# STM32F103T8.net
KiCad netlist of a schematic drawn in Altium Designer
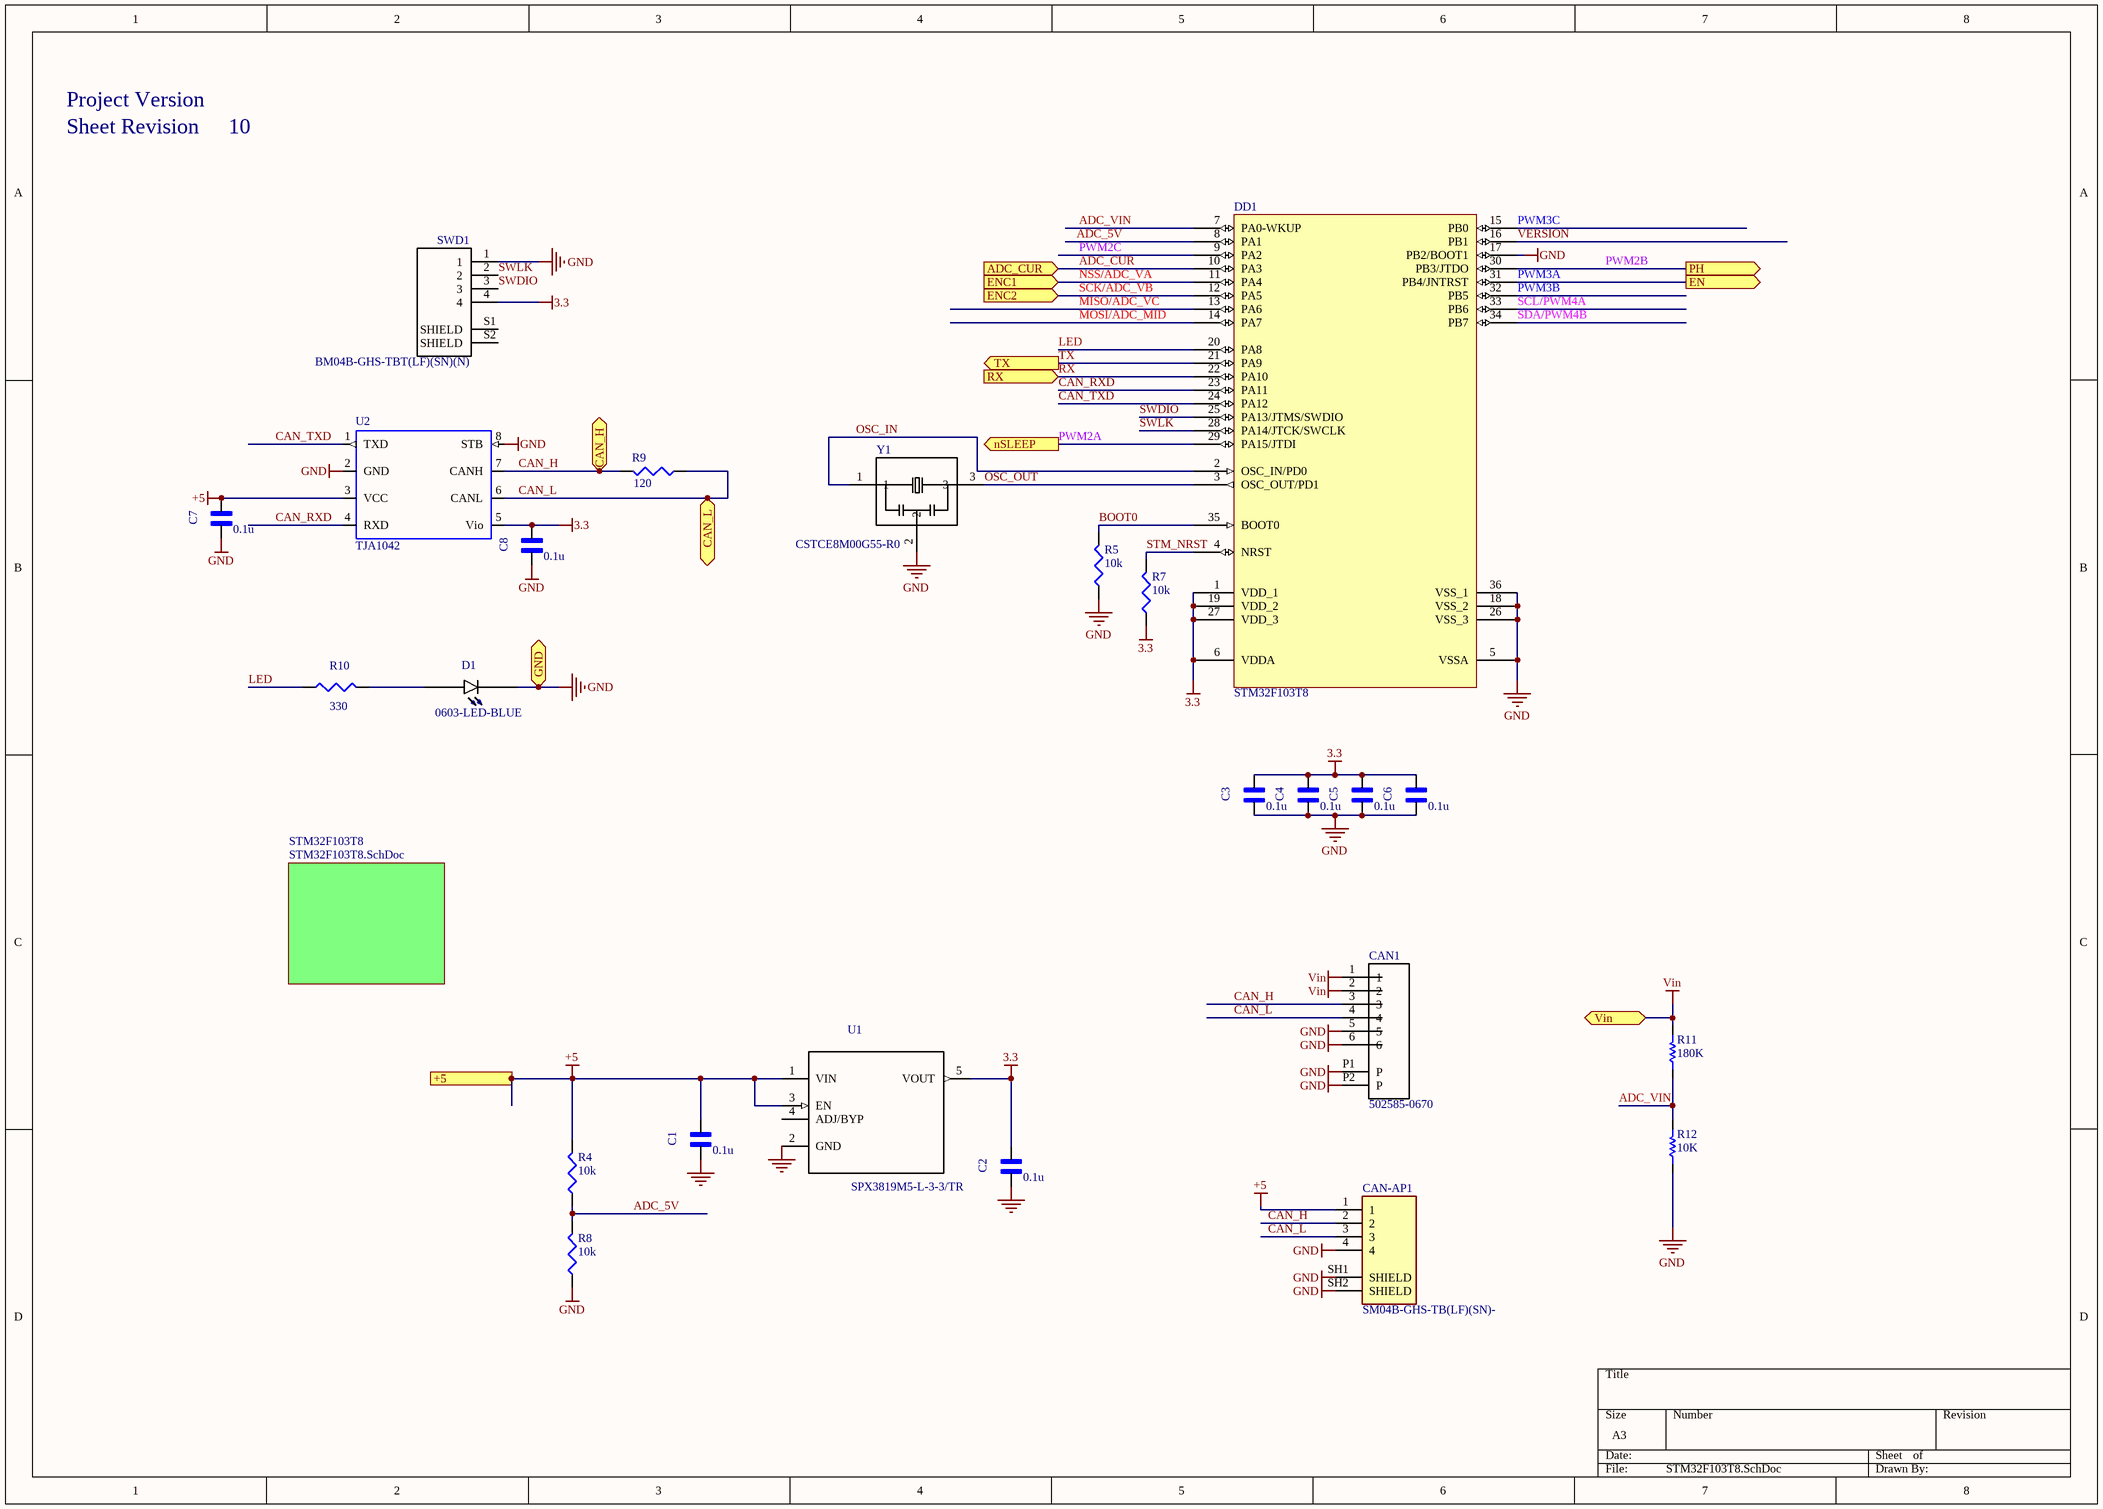
[diagram p0: STM32F103T8.SchDoc]

(export (version "E")
  (design (tool "Eeschema 10.0.6"))
  (components
    (comp (ref "C1")
      (value "0.1u")
      (footprint "*CAPC1608X90")
      (description "Cap Thin Film 0.1uf 50v 0603")
      (fields (field (name "MF") "AVX") (field (name "MP") "GX035C104MAT2-500"))
      (libsource (lib "lib") (part "GX035C104MAT2-500"))
    )
    (comp (ref "C2")
      (value "0.1u")
      (footprint "*CAPC1608X90")
      (description "Cap Thin Film 0.1uf 50v 0603")
      (fields (field (name "MF") "AVX") (field (name "MP") "GX035C104MAT2-500"))
      (libsource (lib "lib") (part "GX035C104MAT2-500"))
    )
    (comp (ref "C3")
      (value "0.1u")
      (footprint "*CAPC1608X90")
      (description "Cap Thin Film 0.1uf 50v 0603")
      (fields (field (name "MF") "AVX") (field (name "MP") "GX035C104MAT2-500 or CL10B104JB8NNNC"))
      (libsource (lib "lib") (part "GX035C104MAT2-500"))
    )
    (comp (ref "C4")
      (value "0.1u")
      (footprint "*CAPC1608X90")
      (description "Cap Thin Film 0.1uf 50v 0603")
      (fields (field (name "MF") "AVX") (field (name "MP") "GX035C104MAT2-500 or CL10B104JB8NNNC"))
      (libsource (lib "lib") (part "GX035C104MAT2-500"))
    )
    (comp (ref "C5")
      (value "0.1u")
      (footprint "*CAPC1608X90")
      (description "Cap Thin Film 0.1uf 50v 0603")
      (fields (field (name "MF") "AVX") (field (name "MP") "GX035C104MAT2-500 or CL10B104JB8NNNC"))
      (libsource (lib "lib") (part "GX035C104MAT2-500"))
    )
    (comp (ref "C6")
      (value "0.1u")
      (footprint "*CAPC1608X90")
      (description "Cap Thin Film 0.1uf 50v 0603")
      (fields (field (name "MF") "AVX") (field (name "MP") "GX035C104MAT2-500 or CL10B104JB8NNNC"))
      (libsource (lib "lib") (part "GX035C104MAT2-500"))
    )
    (comp (ref "C7")
      (value "0.1u")
      (footprint "*CAPC1608X90")
      (description "Cap Thin Film 0.1uf 50v 0603")
      (fields (field (name "MF") "AVX") (field (name "MP") "GX035C104MAT2-500 or CL10B104JB8NNNC"))
      (libsource (lib "lib") (part "GX035C104MAT2-500"))
    )
    (comp (ref "C8")
      (value "0.1u")
      (footprint "*CAPC1608X90")
      (description "Cap Thin Film 0.1uf 50v 0603")
      (fields (field (name "MF") "AVX") (field (name "MP") "GX035C104MAT2-500 or CL10B104JB8NNNC"))
      (libsource (lib "lib") (part "GX035C104MAT2-500"))
    )
    (comp (ref "CAN-AP1")
      (value "SM04B-GHS-TB(LF)(SN)-")
      (footprint "JST_SM04B-GHS-TB(LF)(SN)-")
      (description "Connector Header Surface Mount, Right Angle 4 position 0.049 _1.25mm_")
      (fields (field (name "MP") "SM04B-GHS-TB(LF)(SN)") (field (name "MF") "JST Sales"))
      (libsource (lib "lib") (part "SM04B-GHS-TB(LF)(SN)-"))
    )
    (comp (ref "CAN1")
      (value "502585-0670")
      (footprint "MOLEX_502585-0670")
      (fields (field (name "MF") "Molex"))
      (libsource (lib "lib") (part "502585-0670"))
    )
    (comp (ref "D1")
      (value "0603-LED-BLUE")
      (footprint "*LEDM1608X80_LTE-C1906R-14(Primary)")
      (description "LED IrLED Chip LED 2-Pin SMD T/R")
      (libsource (lib "lib") (part "LTE-C1906R-14"))
    )
    (comp (ref "DD1")
      (value "STM32F103T8")
      (footprint "*QFN50P600X600X100-37N")
      (description "STM32F103T8U6, Микроконтроллер 32BIT ARM 64K FLASH [VFQFPN-36]")
      (fields (field (name "MF") "STM") (field (name "MP") "STM32F103T8U6"))
      (libsource (lib "lib") (part "STM32F103T8"))
    )
    (comp (ref "R4")
      (value "10k")
      (footprint "J1-0603")
      (description "10 kOhms 1 0.1 W 1 10 W Chip Resistor 0603 1608 Metric Thick Film")
      (fields (field (name "MF") "Yageo or NXP") (field (name "MP") "10K 1% 0603"))
      (libsource (lib "CAN_NODE_MINI") (part "RC0603FR-0710KL"))
    )
    (comp (ref "R5")
      (value "10k")
      (footprint "J1-0603")
      (description "10 kOhms 1 0.1 W 1 10 W Chip Resistor 0603 1608 Metric Thick Film")
      (fields (field (name "MF") "Yageo or NXP") (field (name "MP") "10K 1% 0603"))
      (libsource (lib "CAN_NODE_MINI") (part "RC0603FR-0710KL"))
    )
    (comp (ref "R7")
      (value "10k")
      (footprint "J1-0603")
      (description "10 kOhms 1 0.1 W 1 10 W Chip Resistor 0603 1608 Metric Thick Film")
      (fields (field (name "MF") "Yageo or NXP") (field (name "MP") "10K 1% 0603"))
      (libsource (lib "CAN_NODE_MINI") (part "RC0603FR-0710KL"))
    )
    (comp (ref "R8")
      (value "10k")
      (footprint "J1-0603")
      (description "10 kOhms 1 0.1 W 1 10 W Chip Resistor 0603 1608 Metric Thick Film")
      (fields (field (name "MF") "Yageo or NXP") (field (name "MP") "10K 1% 0603"))
      (libsource (lib "CAN_NODE_MINI") (part "RC0603FR-0710KL"))
    )
    (comp (ref "R9")
      (value "120")
      (footprint "J1-0603")
      (description "120 Ohms 1 0.1 W 1 10 W Chip Resistor 0603 1608 Metric Thick Film")
      (fields (field (name "MP") "RC0603FR-07120RL") (field (name "Comment") "Res3"))
      (libsource (lib "Miscellaneous Devices") (part "Res3"))
    )
    (comp (ref "R10")
      (value "330")
      (footprint "J1-0603")
      (description "Resistor")
      (fields (field (name "MP") "RC0603FR-07330RL") (field (name "Comment") "Res3"))
      (libsource (lib "Miscellaneous Devices") (part "Res3"))
    )
    (comp (ref "R11")
      (value "180K")
      (footprint "RES 0603 (1608X06L)")
      (description "Resistor")
      (fields (field (name "TOLERANCE") "5%") (field (name "POWER") "1/8 W"))
      (libsource (lib "R2T Team Library") (part "Resistor"))
    )
    (comp (ref "R12")
      (value "10K")
      (footprint "RES 0603 (1608X06L)")
      (description "Resistor")
      (fields (field (name "TOLERANCE") "5%") (field (name "POWER") "1/8 W"))
      (libsource (lib "R2T Team Library") (part "Resistor"))
    )
    (comp (ref "SWD1")
      (value "BM04B-GHS-TBT(LF)(SN)(N)")
      (footprint "JST_BM04B-GHS-holes")
      (description "Conn Shrouded Header HDR 4 POS 1.25mm Solder ST SMD Reel")
      (fields (field (name "MF") "JST Sales") (field (name "MP") "SM04B-GHS-TB(LF)(SN)"))
      (libsource (lib "lib") (part "BM04B-GHS-TBT(LF)(SN)(N)"))
    )
    (comp (ref "U1")
      (value "SPX3819M5-L-3-3/TR")
      (footprint "*SOT95P280X145-5N")
      (description "Low Dropout Voltage Regulator, Adjustable 0.5A, В±1%, 2.5 to 16 Vin, 5-Pin SOT-23")
      (fields (field (name "MF") "MaxLinear, Inc."))
      (libsource (lib "DC_DC") (part "SPX3819M5-L"))
    )
    (comp (ref "U2")
      (value "TJA1042")
      (footprint "SOT782-1")
      (description "1/1 Transceiver Half CANbus 8-SO")
      (fields (field (name "MF") "NXP USA"))
      (libsource (lib "lib") (part "TJA1042"))
    )
    (comp (ref "Y1")
      (value "CSTCE8M00G55-R0")
      (footprint "*OSC_CSTCE8M00G55-R0")
      (description "Ceramic Resonator 8MHz ??0.5% _Tol_ ??0.2% _Stability_ 33pF 40Ohm 3-Pin CSMD T/R")
      (fields (field (name "MF") "Murata"))
      (libsource (lib "DC_DC") (part "CSTCE8M00G55-R0"))
    )
  )
  (nets
    (net (code "1") (name "+5") (class "Default")
      (node (ref "C1") (pin "1") (pinfunction "1_1") (pintype "passive"))
      (node (ref "C7") (pin "1") (pinfunction "1_1") (pintype "passive"))
      (node (ref "CAN-AP1") (pin "1") (pinfunction "1_1") (pintype "passive"))
      (node (ref "R4") (pin "2") (pinfunction "2_2") (pintype "passive"))
      (node (ref "U1") (pin "1") (pinfunction "VIN_1") (pintype "power_in"))
      (node (ref "U1") (pin "3") (pinfunction "EN_3") (pintype "input"))
      (node (ref "U2") (pin "3") (pinfunction "VCC_3") (pintype "power_in"))
    )
    (net (code "2") (name "/ADC_5V") (class "Default")
      (node (ref "DD1") (pin "8") (pinfunction "PA1_8") (pintype "bidirectional"))
      (node (ref "R4") (pin "1") (pinfunction "1_1") (pintype "passive"))
      (node (ref "R8") (pin "2") (pinfunction "2_2") (pintype "passive"))
    )
    (net (code "3") (name "/ADC_CUR") (class "Default")
      (node (ref "DD1") (pin "10") (pinfunction "PA3_10") (pintype "bidirectional"))
    )
    (net (code "4") (name "/ADC_VIN") (class "Default")
      (node (ref "DD1") (pin "7") (pinfunction "PA0-WKUP_7") (pintype "bidirectional"))
      (node (ref "R11") (pin "1") (pinfunction "1_1") (pintype "passive"))
      (node (ref "R12") (pin "2") (pinfunction "2_2") (pintype "passive"))
    )
    (net (code "5") (name "/BOOT0") (class "Default")
      (node (ref "DD1") (pin "35") (pinfunction "BOOT0_35") (pintype "input"))
      (node (ref "R5") (pin "2") (pinfunction "2_2") (pintype "passive"))
    )
    (net (code "6") (name "/CAN_H") (class "Default")
      (node (ref "CAN-AP1") (pin "2") (pinfunction "2_2") (pintype "passive"))
      (node (ref "CAN1") (pin "3") (pinfunction "3_3") (pintype "passive"))
      (node (ref "R9") (pin "2") (pinfunction "2_2") (pintype "passive"))
      (node (ref "U2") (pin "7") (pinfunction "CANH_7") (pintype "bidirectional"))
    )
    (net (code "7") (name "/CAN_L") (class "Default")
      (node (ref "CAN-AP1") (pin "3") (pinfunction "3_3") (pintype "passive"))
      (node (ref "CAN1") (pin "4") (pinfunction "4_4") (pintype "passive"))
      (node (ref "R9") (pin "1") (pinfunction "1_1") (pintype "passive"))
      (node (ref "U2") (pin "6") (pinfunction "CANL_6") (pintype "bidirectional"))
    )
    (net (code "8") (name "/CAN_RXD") (class "Default")
      (node (ref "DD1") (pin "23") (pinfunction "PA11_23") (pintype "bidirectional"))
      (node (ref "U2") (pin "4") (pinfunction "RXD_4") (pintype "bidirectional"))
    )
    (net (code "9") (name "/CAN_TXD") (class "Default")
      (node (ref "DD1") (pin "24") (pinfunction "PA12_24") (pintype "bidirectional"))
      (node (ref "U2") (pin "1") (pinfunction "TXD_1") (pintype "output"))
    )
    (net (code "10") (name "/EN") (class "Default")
      (node (ref "DD1") (pin "31") (pinfunction "PB4/JNTRST_31") (pintype "bidirectional"))
    )
    (net (code "11") (name "/LED") (class "Default")
      (node (ref "DD1") (pin "20") (pinfunction "PA8_20") (pintype "bidirectional"))
      (node (ref "R10") (pin "1") (pinfunction "1_1") (pintype "passive"))
    )
    (net (code "12") (name "/MISO{slash}ADC_VC") (class "Default")
      (node (ref "DD1") (pin "13") (pinfunction "PA6_13") (pintype "bidirectional"))
    )
    (net (code "13") (name "/MOSI{slash}ADC_MID") (class "Default")
      (node (ref "DD1") (pin "14") (pinfunction "PA7_14") (pintype "bidirectional"))
    )
    (net (code "14") (name "/NSS{slash}ADC_VA") (class "Default")
      (node (ref "DD1") (pin "11") (pinfunction "PA4_11") (pintype "bidirectional"))
    )
    (net (code "15") (name "/OSC_IN") (class "Default")
      (node (ref "DD1") (pin "2") (pinfunction "OSC_IN/PD0_2") (pintype "input"))
      (node (ref "Y1") (pin "1") (pinfunction "1_1") (pintype "passive"))
    )
    (net (code "16") (name "/OSC_OUT") (class "Default")
      (node (ref "DD1") (pin "3") (pinfunction "OSC_OUT/PD1_3") (pintype "output"))
      (node (ref "Y1") (pin "3") (pinfunction "3_3") (pintype "passive"))
    )
    (net (code "17") (name "/PH") (class "Default")
      (node (ref "DD1") (pin "30") (pinfunction "PB3/JTDO_30") (pintype "bidirectional"))
    )
    (net (code "18") (name "/PWM2A") (class "Default")
      (node (ref "DD1") (pin "29") (pinfunction "PA15/JTDI_29") (pintype "bidirectional"))
    )
    (net (code "20") (name "/PWM2C") (class "Default")
      (node (ref "DD1") (pin "9") (pinfunction "PA2_9") (pintype "bidirectional"))
    )
    (net (code "22") (name "/PWM3B") (class "Default")
      (node (ref "DD1") (pin "32") (pinfunction "PB5_32") (pintype "bidirectional"))
    )
    (net (code "23") (name "/PWM3C") (class "Default")
      (node (ref "DD1") (pin "15") (pinfunction "PB0_15") (pintype "bidirectional"))
    )
    (net (code "24") (name "/RX") (class "Default")
      (node (ref "DD1") (pin "22") (pinfunction "PA10_22") (pintype "bidirectional"))
    )
    (net (code "25") (name "/SCK{slash}ADC_VB") (class "Default")
      (node (ref "DD1") (pin "12") (pinfunction "PA5_12") (pintype "bidirectional"))
    )
    (net (code "26") (name "/SCL{slash}PWM4A") (class "Default")
      (node (ref "DD1") (pin "33") (pinfunction "PB6_33") (pintype "bidirectional"))
    )
    (net (code "27") (name "/SDA{slash}PWM4B") (class "Default")
      (node (ref "DD1") (pin "34") (pinfunction "PB7_34") (pintype "bidirectional"))
    )
    (net (code "28") (name "/STM_NRST") (class "Default")
      (node (ref "DD1") (pin "4") (pinfunction "NRST_4") (pintype "bidirectional"))
      (node (ref "R7") (pin "2") (pinfunction "2_2") (pintype "passive"))
    )
    (net (code "29") (name "/SWDIO") (class "Default")
      (node (ref "DD1") (pin "25") (pinfunction "PA13/JTMS/SWDIO_25") (pintype "bidirectional"))
      (node (ref "SWD1") (pin "3") (pinfunction "3_3") (pintype "passive"))
    )
    (net (code "30") (name "/SWLK") (class "Default")
      (node (ref "DD1") (pin "28") (pinfunction "PA14/JTCK/SWCLK_28") (pintype "bidirectional"))
      (node (ref "SWD1") (pin "2") (pinfunction "2_2") (pintype "passive"))
    )
    (net (code "31") (name "/TX") (class "Default")
      (node (ref "DD1") (pin "21") (pinfunction "PA9_21") (pintype "bidirectional"))
    )
    (net (code "32") (name "/VERSION") (class "Default")
      (node (ref "DD1") (pin "16") (pinfunction "PB1_16") (pintype "bidirectional"))
    )
    (net (code "33") (name "3.3") (class "Default")
      (node (ref "C2") (pin "1") (pinfunction "1_1") (pintype "passive"))
      (node (ref "C3") (pin "1") (pinfunction "1_1") (pintype "passive"))
      (node (ref "C4") (pin "1") (pinfunction "1_1") (pintype "passive"))
      (node (ref "C5") (pin "1") (pinfunction "1_1") (pintype "passive"))
      (node (ref "C6") (pin "1") (pinfunction "1_1") (pintype "passive"))
      (node (ref "C8") (pin "1") (pinfunction "1_1") (pintype "passive"))
      (node (ref "DD1") (pin "1") (pinfunction "VDD_1_1") (pintype "power_in"))
      (node (ref "DD1") (pin "19") (pinfunction "VDD_2_19") (pintype "power_in"))
      (node (ref "DD1") (pin "27") (pinfunction "VDD_3_27") (pintype "power_in"))
      (node (ref "DD1") (pin "6") (pinfunction "VDDA_6") (pintype "power_in"))
      (node (ref "R7") (pin "1") (pinfunction "1_1") (pintype "passive"))
      (node (ref "SWD1") (pin "4") (pinfunction "4_4") (pintype "passive"))
      (node (ref "U1") (pin "5") (pinfunction "VOUT_5") (pintype "output"))
      (node (ref "U2") (pin "5") (pinfunction "Vio_5") (pintype "power_in"))
    )
    (net (code "34") (name "GND") (class "Default")
      (node (ref "C1") (pin "2") (pinfunction "2_2") (pintype "passive"))
      (node (ref "C2") (pin "2") (pinfunction "2_2") (pintype "passive"))
      (node (ref "C3") (pin "2") (pinfunction "2_2") (pintype "passive"))
      (node (ref "C4") (pin "2") (pinfunction "2_2") (pintype "passive"))
      (node (ref "C5") (pin "2") (pinfunction "2_2") (pintype "passive"))
      (node (ref "C6") (pin "2") (pinfunction "2_2") (pintype "passive"))
      (node (ref "C7") (pin "2") (pinfunction "2_2") (pintype "passive"))
      (node (ref "C8") (pin "2") (pinfunction "2_2") (pintype "passive"))
      (node (ref "CAN-AP1") (pin "4") (pinfunction "4_4") (pintype "passive"))
      (node (ref "CAN-AP1") (pin "SH1") (pinfunction "SHIELD_SH1") (pintype "power_in"))
      (node (ref "CAN-AP1") (pin "SH2") (pinfunction "SHIELD_SH2") (pintype "power_in"))
      (node (ref "CAN1") (pin "5") (pinfunction "5_5") (pintype "passive"))
      (node (ref "CAN1") (pin "6") (pinfunction "6_6") (pintype "passive"))
      (node (ref "CAN1") (pin "P1") (pinfunction "P_P1") (pintype "passive"))
      (node (ref "CAN1") (pin "P2") (pinfunction "P_P2") (pintype "passive"))
      (node (ref "D1") (pin "C") (pinfunction "C_C") (pintype "passive"))
      (node (ref "DD1") (pin "17") (pinfunction "PB2/BOOT1_17") (pintype "bidirectional"))
      (node (ref "DD1") (pin "18") (pinfunction "VSS_2_18") (pintype "power_in"))
      (node (ref "DD1") (pin "26") (pinfunction "VSS_3_26") (pintype "power_in"))
      (node (ref "DD1") (pin "36") (pinfunction "VSS_1_36") (pintype "power_in"))
      (node (ref "DD1") (pin "5") (pinfunction "VSSA_5") (pintype "power_in"))
      (node (ref "R12") (pin "1") (pinfunction "1_1") (pintype "passive"))
      (node (ref "R5") (pin "1") (pinfunction "1_1") (pintype "passive"))
      (node (ref "R8") (pin "1") (pinfunction "1_1") (pintype "passive"))
      (node (ref "SWD1") (pin "1") (pinfunction "1_1") (pintype "passive"))
      (node (ref "U1") (pin "2") (pinfunction "GND_2") (pintype "passive"))
      (node (ref "U2") (pin "2") (pinfunction "GND_2") (pintype "power_in"))
      (node (ref "U2") (pin "8") (pinfunction "STB_8") (pintype "input"))
      (node (ref "Y1") (pin "2") (pinfunction "2_2") (pintype "power_in"))
    )
    (net (code "35") (name "Net-(D1-PadA)") (class "Default")
      (node (ref "D1") (pin "A") (pinfunction "A_A") (pintype "passive"))
      (node (ref "R10") (pin "2") (pinfunction "2_2") (pintype "passive"))
    )
    (net (code "36") (name "Vin") (class "Default")
      (node (ref "CAN1") (pin "1") (pinfunction "1_1") (pintype "passive"))
      (node (ref "CAN1") (pin "2") (pinfunction "2_2") (pintype "passive"))
      (node (ref "R11") (pin "2") (pinfunction "2_2") (pintype "passive"))
    )
    (net (code "37") (name "unconnected-(SWD1-SHIELD-PadS1)") (class "Default")
      (node (ref "SWD1") (pin "S1") (pinfunction "SHIELD_S1") (pintype "passive"))
    )
    (net (code "38") (name "unconnected-(SWD1-SHIELD-PadS2)") (class "Default")
      (node (ref "SWD1") (pin "S2") (pinfunction "SHIELD_S2") (pintype "passive"))
    )
    (net (code "39") (name "unconnected-(U1-ADJ{slash}BYP-Pad4)") (class "Default")
      (node (ref "U1") (pin "4") (pinfunction "ADJ/BYP_4") (pintype "passive"))
    )
  )
)
